# team4-selo-atmega32u4.net
KiCad netlist of a schematic drawn in EAGLE
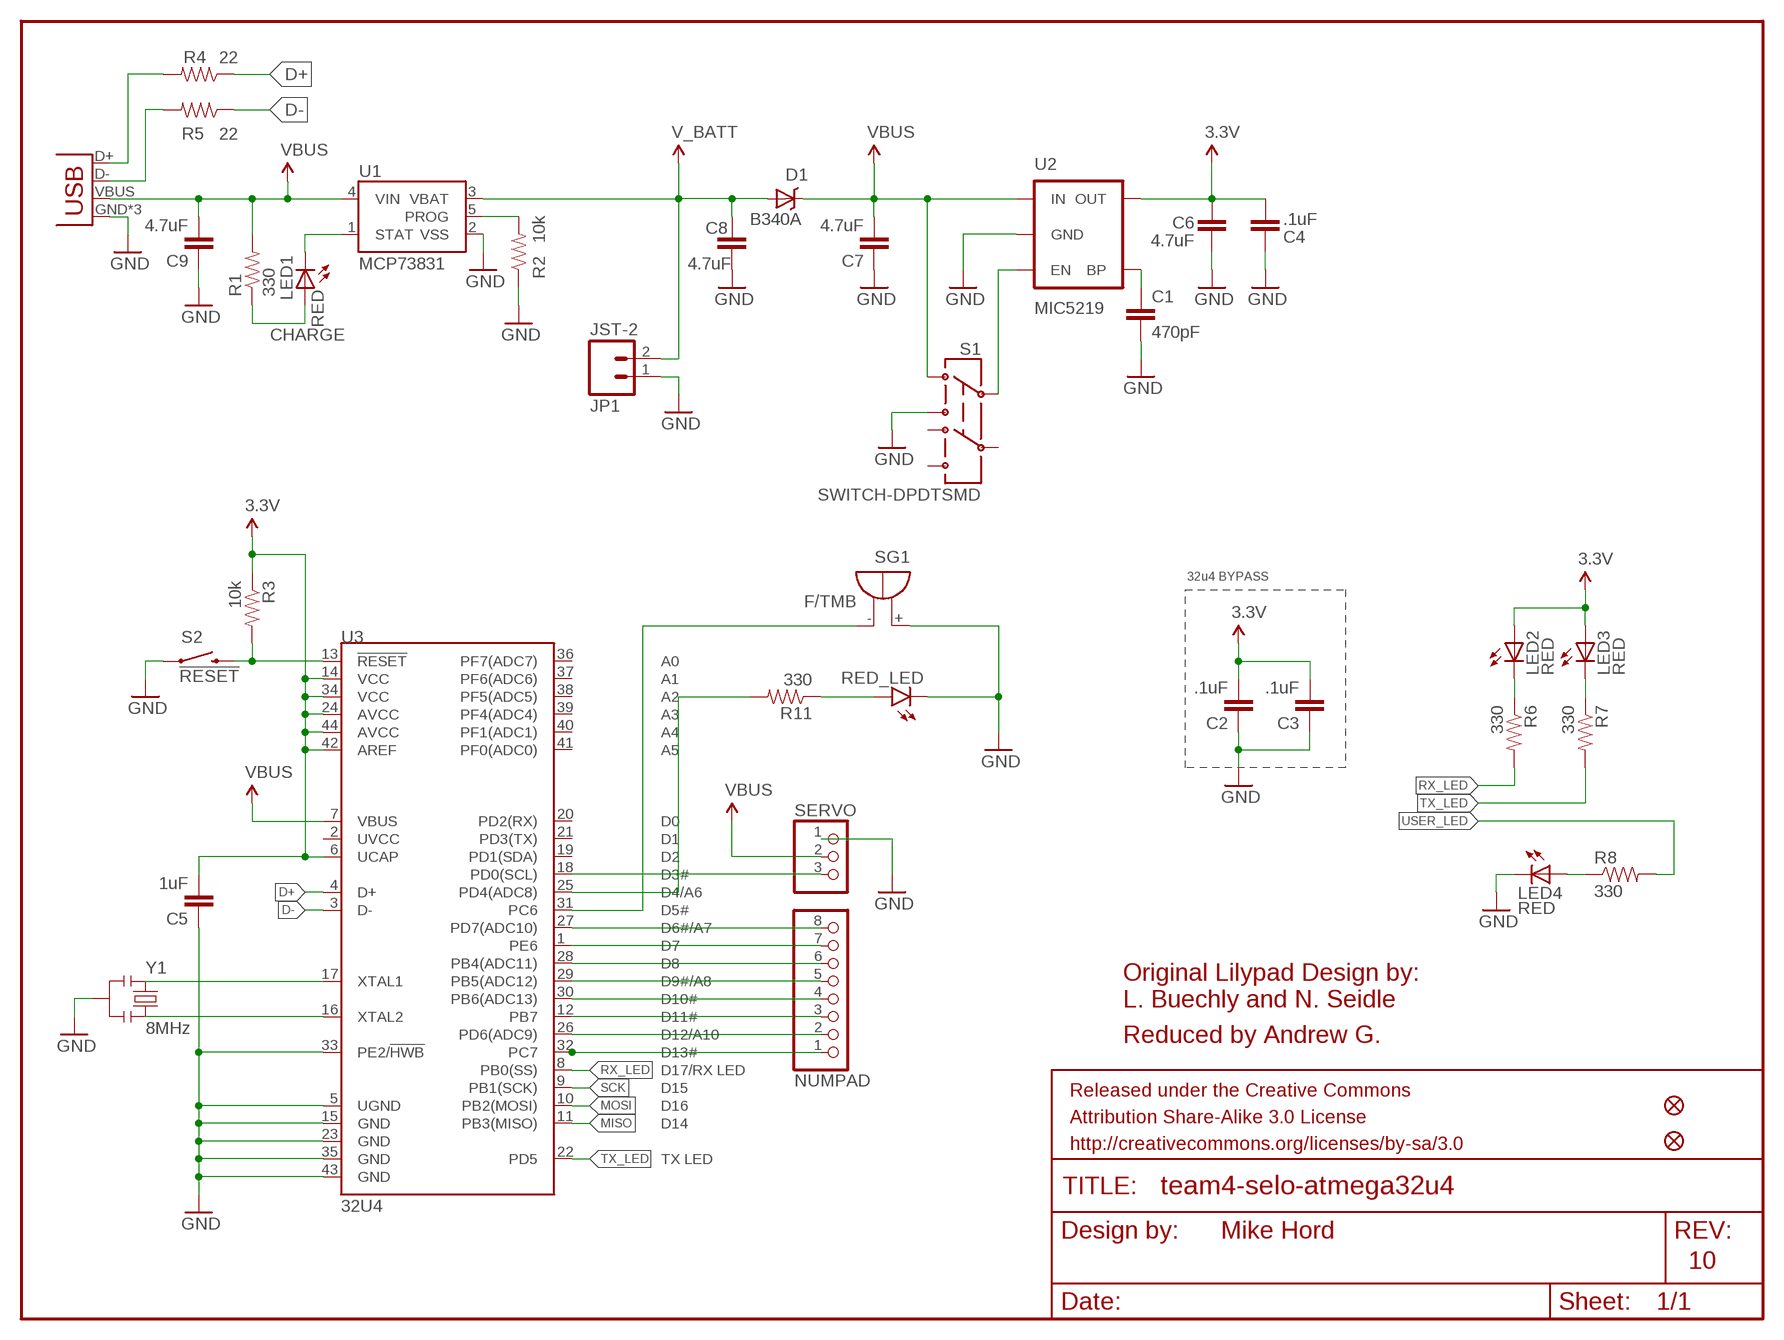
[diagram p0: schematic, sheet 1]

(export (version "E")
  (design (tool "Eeschema 10.0.6"))
  (components
    (comp (ref "C1")
      (value "470pF")
      (footprint "eagle-import:0603-CAP")
      (libsource (lib "eagle-import") (part "CAP0603-CAP"))
    )
    (comp (ref "C2")
      (value ".1uF")
      (footprint "eagle-import:0603-CAP")
      (libsource (lib "eagle-import") (part "CAP0603-CAP"))
    )
    (comp (ref "C3")
      (value ".1uF")
      (footprint "eagle-import:0603-CAP")
      (libsource (lib "eagle-import") (part "CAP0603-CAP"))
    )
    (comp (ref "C4")
      (value ".1uF")
      (footprint "eagle-import:0603-CAP")
      (libsource (lib "eagle-import") (part "CAP0603-CAP"))
    )
    (comp (ref "C5")
      (value "1uF")
      (footprint "eagle-import:0603-CAP")
      (libsource (lib "eagle-import") (part "CAP0603-CAP"))
    )
    (comp (ref "C6")
      (value "4.7uF")
      (footprint "eagle-import:0603-CAP")
      (libsource (lib "eagle-import") (part "CAP0603-CAP"))
    )
    (comp (ref "C7")
      (value "4.7uF")
      (footprint "eagle-import:1206")
      (libsource (lib "eagle-import") (part "CAP1206"))
    )
    (comp (ref "C8")
      (value "4.7uF")
      (footprint "eagle-import:1206")
      (libsource (lib "eagle-import") (part "CAP1206"))
    )
    (comp (ref "C9")
      (value "4.7uF")
      (footprint "eagle-import:1206")
      (libsource (lib "eagle-import") (part "CAP1206"))
    )
    (comp (ref "D1")
      (value "B340A")
      (footprint "eagle-import:SMA-DIODE")
      (libsource (lib "eagle-import") (part "DIODE-SCHOTTKY_"))
    )
    (comp (ref "JP1")
      (value "JST-2")
      (footprint "eagle-import:JST-2-SMD")
      (libsource (lib "eagle-import") (part "M02-JST-2MM-SMT"))
    )
    (comp (ref "JP2")
      (value "FIDUCIALUFIDUCIAL")
      (footprint "eagle-import:MICRO-FIDUCIAL")
      (libsource (lib "eagle-import") (part "FIDUCIALUFIDUCIAL"))
    )
    (comp (ref "JP3")
      (value "FIDUCIALUFIDUCIAL")
      (footprint "eagle-import:MICRO-FIDUCIAL")
      (libsource (lib "eagle-import") (part "FIDUCIALUFIDUCIAL"))
    )
    (comp (ref "LED1")
      (value "RED")
      (footprint "eagle-import:LED-0603")
      (libsource (lib "eagle-import") (part "LED0603"))
    )
    (comp (ref "LED2")
      (value "RED")
      (footprint "eagle-import:LED-0603")
      (libsource (lib "eagle-import") (part "LED0603"))
    )
    (comp (ref "LED3")
      (value "RED")
      (footprint "eagle-import:LED-0603")
      (libsource (lib "eagle-import") (part "LED0603"))
    )
    (comp (ref "LED4")
      (value "RED")
      (footprint "eagle-import:LED-0603")
      (libsource (lib "eagle-import") (part "LED0603"))
    )
    (comp (ref "NUMPAD")
      (value "PINHD-1X8")
      (footprint "eagle-import:1X08")
      (libsource (lib "eagle-import") (part "PINHD-1X8"))
    )
    (comp (ref "R1")
      (value "330")
      (footprint "eagle-import:0603-RES")
      (libsource (lib "eagle-import") (part "RESISTOR0603-RES"))
    )
    (comp (ref "R2")
      (value "10k")
      (footprint "eagle-import:0603-RES")
      (libsource (lib "eagle-import") (part "RESISTOR0603-RES"))
    )
    (comp (ref "R3")
      (value "10k")
      (footprint "eagle-import:0603-RES")
      (libsource (lib "eagle-import") (part "RESISTOR0603-RES"))
    )
    (comp (ref "R4")
      (value "22")
      (footprint "eagle-import:0603-RES")
      (libsource (lib "eagle-import") (part "RESISTOR0603-RES"))
    )
    (comp (ref "R5")
      (value "22")
      (footprint "eagle-import:0603-RES")
      (libsource (lib "eagle-import") (part "RESISTOR0603-RES"))
    )
    (comp (ref "R6")
      (value "330")
      (footprint "eagle-import:0603-RES")
      (libsource (lib "eagle-import") (part "RESISTOR0603-RES"))
    )
    (comp (ref "R7")
      (value "330")
      (footprint "eagle-import:0603-RES")
      (libsource (lib "eagle-import") (part "RESISTOR0603-RES"))
    )
    (comp (ref "R8")
      (value "330")
      (footprint "eagle-import:0603-RES")
      (libsource (lib "eagle-import") (part "RESISTOR0603-RES"))
    )
    (comp (ref "R11")
      (value "330")
      (footprint "eagle-import:0603-RES")
      (libsource (lib "eagle-import") (part "RESISTOR0603-RES"))
    )
    (comp (ref "RED_LED")
      (value "LED5MM")
      (footprint "eagle-import:LED5MM")
      (libsource (lib "eagle-import") (part "led_259_LED5MM"))
    )
    (comp (ref "S1")
      (value "SWITCH-DPDTSMD")
      (footprint "eagle-import:AYZ0202")
      (libsource (lib "eagle-import") (part "SWITCH-DPDTSMD"))
    )
    (comp (ref "S2")
      (value "!RESET")
      (footprint "eagle-import:TACTILE_SWITCH_SMD")
      (libsource (lib "eagle-import") (part "SWITCH-MOMENTARY-2SMD"))
    )
    (comp (ref "SERVO")
      (value "PINHD-1X3")
      (footprint "eagle-import:1X03")
      (libsource (lib "eagle-import") (part "PINHD-1X3"))
    )
    (comp (ref "SG1")
      (value "F/TMB")
      (footprint "eagle-import:F_TMB")
      (libsource (lib "eagle-import") (part "F/TMB"))
    )
    (comp (ref "U1")
      (value "MCP73831")
      (footprint "eagle-import:SOT23-5")
      (libsource (lib "eagle-import") (part "MCP73831"))
    )
    (comp (ref "U2")
      (value "MIC5219")
      (footprint "eagle-import:SOT23-5")
      (libsource (lib "eagle-import") (part "V_REG_MIC5219SMD"))
    )
    (comp (ref "U3")
      (value "32U4")
      (footprint "eagle-import:TQFP44")
      (fields (field (name "PROD_ID") "IC-10828"))
      (libsource (lib "eagle-import") (part "ATMEGA32U4TQFP-44"))
    )
    (comp (ref "X1")
      (value "USB-MICROB")
      (footprint "eagle-import:USB-MICROB")
      (libsource (lib "eagle-import") (part "USB-MICROB"))
    )
    (comp (ref "Y1")
      (value "8MHz")
      (footprint "eagle-import:RESONATOR-SMD")
      (libsource (lib "eagle-import") (part "RESONATORSMD"))
    )
  )
  (nets
    (net (code "1") (name "3.3V") (class "Default")
      (node (ref "C2") (pin "2") (pinfunction "2_2") (pintype "passive"))
      (node (ref "C3") (pin "2") (pinfunction "2_2") (pintype "passive"))
      (node (ref "C4") (pin "2") (pinfunction "2_2") (pintype "passive"))
      (node (ref "C5") (pin "2") (pinfunction "2_2") (pintype "passive"))
      (node (ref "C6") (pin "2") (pinfunction "2_2") (pintype "passive"))
      (node (ref "LED2") (pin "A") (pinfunction "A_A") (pintype "passive"))
      (node (ref "LED3") (pin "A") (pinfunction "A_A") (pintype "passive"))
      (node (ref "R3") (pin "1") (pinfunction "1_1") (pintype "passive"))
      (node (ref "U2") (pin "5") (pinfunction "OUT_5") (pintype "passive"))
      (node (ref "U3") (pin "14") (pinfunction "VCC_14") (pintype "bidirectional"))
      (node (ref "U3") (pin "24") (pinfunction "AVCC_24") (pintype "bidirectional"))
      (node (ref "U3") (pin "34") (pinfunction "VCC_34") (pintype "bidirectional"))
      (node (ref "U3") (pin "42") (pinfunction "AREF_42") (pintype "bidirectional"))
      (node (ref "U3") (pin "44") (pinfunction "AVCC_44") (pintype "bidirectional"))
      (node (ref "U3") (pin "6") (pinfunction "UCAP_6") (pintype "bidirectional"))
    )
    (net (code "2") (name "D+") (class "Default")
      (node (ref "R4") (pin "1") (pinfunction "1_1") (pintype "passive"))
      (node (ref "U3") (pin "4") (pinfunction "D+_4") (pintype "bidirectional"))
    )
    (net (code "3") (name "D-") (class "Default")
      (node (ref "R5") (pin "1") (pinfunction "1_1") (pintype "passive"))
      (node (ref "U3") (pin "3") (pinfunction "D-_3") (pintype "bidirectional"))
    )
    (net (code "4") (name "GND") (class "Default")
      (node (ref "C1") (pin "2") (pinfunction "2_2") (pintype "passive"))
      (node (ref "C2") (pin "1") (pinfunction "1_1") (pintype "passive"))
      (node (ref "C3") (pin "1") (pinfunction "1_1") (pintype "passive"))
      (node (ref "C4") (pin "1") (pinfunction "1_1") (pintype "passive"))
      (node (ref "C5") (pin "1") (pinfunction "1_1") (pintype "passive"))
      (node (ref "C6") (pin "1") (pinfunction "1_1") (pintype "passive"))
      (node (ref "C7") (pin "1") (pinfunction "1_1") (pintype "passive"))
      (node (ref "C8") (pin "1") (pinfunction "1_1") (pintype "passive"))
      (node (ref "C9") (pin "1") (pinfunction "1_1") (pintype "passive"))
      (node (ref "JP1") (pin "1") (pinfunction "2_1") (pintype "passive"))
      (node (ref "LED4") (pin "C") (pinfunction "C_C") (pintype "passive"))
      (node (ref "R2") (pin "1") (pinfunction "1_1") (pintype "passive"))
      (node (ref "RED_LED") (pin "K") (pinfunction "C_K") (pintype "passive"))
      (node (ref "S1") (pin "3") (pinfunction "3_3") (pintype "bidirectional"))
      (node (ref "S2") (pin "1") (pinfunction "1_1") (pintype "passive"))
      (node (ref "SERVO") (pin "1") (pinfunction "1_1") (pintype "passive"))
      (node (ref "SG1") (pin "+") (pinfunction "+_+") (pintype "passive"))
      (node (ref "U1") (pin "2") (pinfunction "VSS_2") (pintype "power_in"))
      (node (ref "U2") (pin "2") (pinfunction "GND_2") (pintype "input"))
      (node (ref "U3") (pin "15") (pinfunction "GND_15") (pintype "bidirectional"))
      (node (ref "U3") (pin "23") (pinfunction "GND_23") (pintype "bidirectional"))
      (node (ref "U3") (pin "33") (pinfunction "PE2/~{HWB}_33") (pintype "bidirectional"))
      (node (ref "U3") (pin "35") (pinfunction "GND_35") (pintype "bidirectional"))
      (node (ref "U3") (pin "43") (pinfunction "GND_43") (pintype "bidirectional"))
      (node (ref "U3") (pin "5") (pinfunction "UGND_5") (pintype "bidirectional"))
      (node (ref "X1") (pin "GND") (pinfunction "GND_GND") (pintype "bidirectional"))
      (node (ref "X1") (pin "MT1") (pinfunction "GND_MT1") (pintype "bidirectional"))
      (node (ref "X1") (pin "MT2") (pinfunction "GND_MT2") (pintype "bidirectional"))
      (node (ref "Y1") (pin "2") (pinfunction "2_2") (pintype "passive"))
    )
    (net (code "5") (name "MISO") (class "Default")
      (node (ref "U3") (pin "11") (pinfunction "PB3(MISO)_11") (pintype "bidirectional"))
    )
    (net (code "6") (name "MOSI") (class "Default")
      (node (ref "U3") (pin "10") (pinfunction "PB2(MOSI)_10") (pintype "bidirectional"))
    )
    (net (code "7") (name "Net-(LED1-PadA)") (class "Default")
      (node (ref "LED1") (pin "A") (pinfunction "A_A") (pintype "passive"))
      (node (ref "R1") (pin "1") (pinfunction "1_1") (pintype "passive"))
    )
    (net (code "8") (name "Net-(LED2-PadC)") (class "Default")
      (node (ref "LED2") (pin "C") (pinfunction "C_C") (pintype "passive"))
      (node (ref "R6") (pin "1") (pinfunction "1_1") (pintype "passive"))
    )
    (net (code "9") (name "Net-(LED3-PadC)") (class "Default")
      (node (ref "LED3") (pin "C") (pinfunction "C_C") (pintype "passive"))
      (node (ref "R7") (pin "1") (pinfunction "1_1") (pintype "passive"))
    )
    (net (code "10") (name "Net-(LED4-PadA)") (class "Default")
      (node (ref "LED4") (pin "A") (pinfunction "A_A") (pintype "passive"))
      (node (ref "R8") (pin "1") (pinfunction "1_1") (pintype "passive"))
    )
    (net (code "11") (name "Net-(R4-Pad2)") (class "Default")
      (node (ref "R4") (pin "2") (pinfunction "2_2") (pintype "passive"))
      (node (ref "X1") (pin "D+") (pinfunction "D+_D+") (pintype "bidirectional"))
    )
    (net (code "12") (name "Net-(R5-Pad2)") (class "Default")
      (node (ref "R5") (pin "2") (pinfunction "2_2") (pintype "passive"))
      (node (ref "X1") (pin "D-") (pinfunction "D-_D-") (pintype "bidirectional"))
    )
    (net (code "13") (name "Net-(R11-Pad1)") (class "Default")
      (node (ref "R11") (pin "1") (pinfunction "1_1") (pintype "passive"))
      (node (ref "RED_LED") (pin "A") (pinfunction "A_A") (pintype "passive"))
    )
    (net (code "14") (name "Net-(S2-2)") (class "Default")
      (node (ref "R3") (pin "2") (pinfunction "2_2") (pintype "passive"))
      (node (ref "S2") (pin "3") (pinfunction "2_3") (pintype "passive"))
      (node (ref "U3") (pin "13") (pinfunction "~{RESET}_13") (pintype "bidirectional"))
    )
    (net (code "15") (name "Net-(U1-PROG)") (class "Default")
      (node (ref "R2") (pin "2") (pinfunction "2_2") (pintype "passive"))
      (node (ref "U1") (pin "5") (pinfunction "PROG_5") (pintype "input"))
    )
    (net (code "16") (name "Net-(U1-STAT)") (class "Default")
      (node (ref "LED1") (pin "C") (pinfunction "C_C") (pintype "passive"))
      (node (ref "U1") (pin "1") (pinfunction "STAT_1") (pintype "output"))
    )
    (net (code "17") (name "Net-(U2-BP)") (class "Default")
      (node (ref "C1") (pin "1") (pinfunction "1_1") (pintype "passive"))
      (node (ref "U2") (pin "4") (pinfunction "BP_4") (pintype "input"))
    )
    (net (code "18") (name "Net-(U2-EN)") (class "Default")
      (node (ref "S1") (pin "2") (pinfunction "2_2") (pintype "bidirectional"))
      (node (ref "U2") (pin "3") (pinfunction "EN_3") (pintype "input"))
    )
    (net (code "19") (name "Net-(U3-PB4(ADC11))") (class "Default")
      (node (ref "NUMPAD") (pin "6") (pinfunction "6_6") (pintype "passive"))
      (node (ref "U3") (pin "28") (pinfunction "PB4(ADC11)_28") (pintype "bidirectional"))
    )
    (net (code "20") (name "Net-(U3-PB5(ADC12))") (class "Default")
      (node (ref "NUMPAD") (pin "5") (pinfunction "5_5") (pintype "passive"))
      (node (ref "U3") (pin "29") (pinfunction "PB5(ADC12)_29") (pintype "bidirectional"))
    )
    (net (code "21") (name "Net-(U3-PB6(ADC13))") (class "Default")
      (node (ref "NUMPAD") (pin "4") (pinfunction "4_4") (pintype "passive"))
      (node (ref "U3") (pin "30") (pinfunction "PB6(ADC13)_30") (pintype "bidirectional"))
    )
    (net (code "22") (name "Net-(U3-PB7)") (class "Default")
      (node (ref "NUMPAD") (pin "3") (pinfunction "3_3") (pintype "passive"))
      (node (ref "U3") (pin "12") (pinfunction "PB7_12") (pintype "bidirectional"))
    )
    (net (code "23") (name "Net-(U3-PC6)") (class "Default")
      (node (ref "SG1") (pin "-") (pinfunction "-_-") (pintype "passive"))
      (node (ref "U3") (pin "31") (pinfunction "PC6_31") (pintype "bidirectional"))
    )
    (net (code "24") (name "Net-(U3-PD0(SCL))") (class "Default")
      (node (ref "SERVO") (pin "3") (pinfunction "3_3") (pintype "passive"))
      (node (ref "U3") (pin "18") (pinfunction "PD0(SCL)_18") (pintype "bidirectional"))
    )
    (net (code "25") (name "Net-(U3-PD4(ADC8))") (class "Default")
      (node (ref "R11") (pin "2") (pinfunction "2_2") (pintype "passive"))
      (node (ref "U3") (pin "25") (pinfunction "PD4(ADC8)_25") (pintype "bidirectional"))
    )
    (net (code "26") (name "Net-(U3-PD6(ADC9))") (class "Default")
      (node (ref "NUMPAD") (pin "2") (pinfunction "2_2") (pintype "passive"))
      (node (ref "U3") (pin "26") (pinfunction "PD6(ADC9)_26") (pintype "bidirectional"))
    )
    (net (code "27") (name "Net-(U3-PD7(ADC10))") (class "Default")
      (node (ref "NUMPAD") (pin "8") (pinfunction "8_8") (pintype "passive"))
      (node (ref "U3") (pin "27") (pinfunction "PD7(ADC10)_27") (pintype "bidirectional"))
    )
    (net (code "28") (name "Net-(U3-PE6)") (class "Default")
      (node (ref "NUMPAD") (pin "7") (pinfunction "7_7") (pintype "passive"))
      (node (ref "U3") (pin "1") (pinfunction "PE6_1") (pintype "bidirectional"))
    )
    (net (code "29") (name "Net-(U3-XTAL1)") (class "Default")
      (node (ref "U3") (pin "17") (pinfunction "XTAL1_17") (pintype "bidirectional"))
      (node (ref "Y1") (pin "1") (pinfunction "1_1") (pintype "passive"))
    )
    (net (code "30") (name "Net-(U3-XTAL2)") (class "Default")
      (node (ref "U3") (pin "16") (pinfunction "XTAL2_16") (pintype "bidirectional"))
      (node (ref "Y1") (pin "3") (pinfunction "3_3") (pintype "passive"))
    )
    (net (code "31") (name "RX_LED") (class "Default")
      (node (ref "R6") (pin "2") (pinfunction "2_2") (pintype "passive"))
      (node (ref "U3") (pin "8") (pinfunction "PB0(SS)_8") (pintype "bidirectional"))
    )
    (net (code "32") (name "SCK") (class "Default")
      (node (ref "U3") (pin "9") (pinfunction "PB1(SCK)_9") (pintype "bidirectional"))
    )
    (net (code "33") (name "TX_LED") (class "Default")
      (node (ref "R7") (pin "2") (pinfunction "2_2") (pintype "passive"))
      (node (ref "U3") (pin "22") (pinfunction "PD5_22") (pintype "bidirectional"))
    )
    (net (code "34") (name "USER_LED") (class "Default")
      (node (ref "NUMPAD") (pin "1") (pinfunction "1_1") (pintype "passive"))
      (node (ref "R8") (pin "2") (pinfunction "2_2") (pintype "passive"))
      (node (ref "U3") (pin "32") (pinfunction "PC7_32") (pintype "bidirectional"))
    )
    (net (code "35") (name "VBUS") (class "Default")
      (node (ref "C7") (pin "2") (pinfunction "2_2") (pintype "passive"))
      (node (ref "C9") (pin "2") (pinfunction "2_2") (pintype "passive"))
      (node (ref "D1") (pin "C") (pinfunction "C_C") (pintype "passive"))
      (node (ref "R1") (pin "2") (pinfunction "2_2") (pintype "passive"))
      (node (ref "S1") (pin "1") (pinfunction "1_1") (pintype "bidirectional"))
      (node (ref "SERVO") (pin "2") (pinfunction "2_2") (pintype "passive"))
      (node (ref "U1") (pin "4") (pinfunction "VIN_4") (pintype "power_in"))
      (node (ref "U2") (pin "1") (pinfunction "IN_1") (pintype "input"))
      (node (ref "U3") (pin "7") (pinfunction "VBUS_7") (pintype "bidirectional"))
      (node (ref "X1") (pin "VBUS") (pinfunction "VBUS_VBUS") (pintype "bidirectional"))
    )
    (net (code "36") (name "V_BATT") (class "Default")
      (node (ref "C8") (pin "2") (pinfunction "2_2") (pintype "passive"))
      (node (ref "D1") (pin "A") (pinfunction "A_A") (pintype "passive"))
      (node (ref "JP1") (pin "2") (pinfunction "1_2") (pintype "passive"))
      (node (ref "U1") (pin "3") (pinfunction "VBAT_3") (pintype "power_in"))
    )
    (net (code "37") (name "unconnected-(S1-Pad4)") (class "Default")
      (node (ref "S1") (pin "4") (pinfunction "4_4") (pintype "bidirectional"))
    )
    (net (code "38") (name "unconnected-(S1-Pad5)") (class "Default")
      (node (ref "S1") (pin "5") (pinfunction "5_5") (pintype "bidirectional"))
    )
    (net (code "39") (name "unconnected-(S1-Pad6)") (class "Default")
      (node (ref "S1") (pin "6") (pinfunction "6_6") (pintype "bidirectional"))
    )
    (net (code "40") (name "unconnected-(U3-PD1(SDA)-Pad19)") (class "Default")
      (node (ref "U3") (pin "19") (pinfunction "PD1(SDA)_19") (pintype "bidirectional"))
    )
    (net (code "41") (name "unconnected-(U3-PD2(RX)-Pad20)") (class "Default")
      (node (ref "U3") (pin "20") (pinfunction "PD2(RX)_20") (pintype "bidirectional"))
    )
    (net (code "42") (name "unconnected-(U3-PD3(TX)-Pad21)") (class "Default")
      (node (ref "U3") (pin "21") (pinfunction "PD3(TX)_21") (pintype "bidirectional"))
    )
    (net (code "43") (name "unconnected-(U3-PF0(ADC0)-Pad41)") (class "Default")
      (node (ref "U3") (pin "41") (pinfunction "PF0(ADC0)_41") (pintype "bidirectional"))
    )
    (net (code "44") (name "unconnected-(U3-PF1(ADC1)-Pad40)") (class "Default")
      (node (ref "U3") (pin "40") (pinfunction "PF1(ADC1)_40") (pintype "bidirectional"))
    )
    (net (code "45") (name "unconnected-(U3-PF4(ADC4)-Pad39)") (class "Default")
      (node (ref "U3") (pin "39") (pinfunction "PF4(ADC4)_39") (pintype "bidirectional"))
    )
    (net (code "46") (name "unconnected-(U3-PF5(ADC5)-Pad38)") (class "Default")
      (node (ref "U3") (pin "38") (pinfunction "PF5(ADC5)_38") (pintype "bidirectional"))
    )
    (net (code "47") (name "unconnected-(U3-PF6(ADC6)-Pad37)") (class "Default")
      (node (ref "U3") (pin "37") (pinfunction "PF6(ADC6)_37") (pintype "bidirectional"))
    )
    (net (code "48") (name "unconnected-(U3-PF7(ADC7)-Pad36)") (class "Default")
      (node (ref "U3") (pin "36") (pinfunction "PF7(ADC7)_36") (pintype "bidirectional"))
    )
    (net (code "49") (name "unconnected-(U3-UVCC-Pad2)") (class "Default")
      (node (ref "U3") (pin "2") (pinfunction "UVCC_2") (pintype "bidirectional"))
    )
  )
)
